# STM32-ROMI_Rev_A_2_3V_5V.net
KiCad netlist of a schematic drawn in Altium Designer
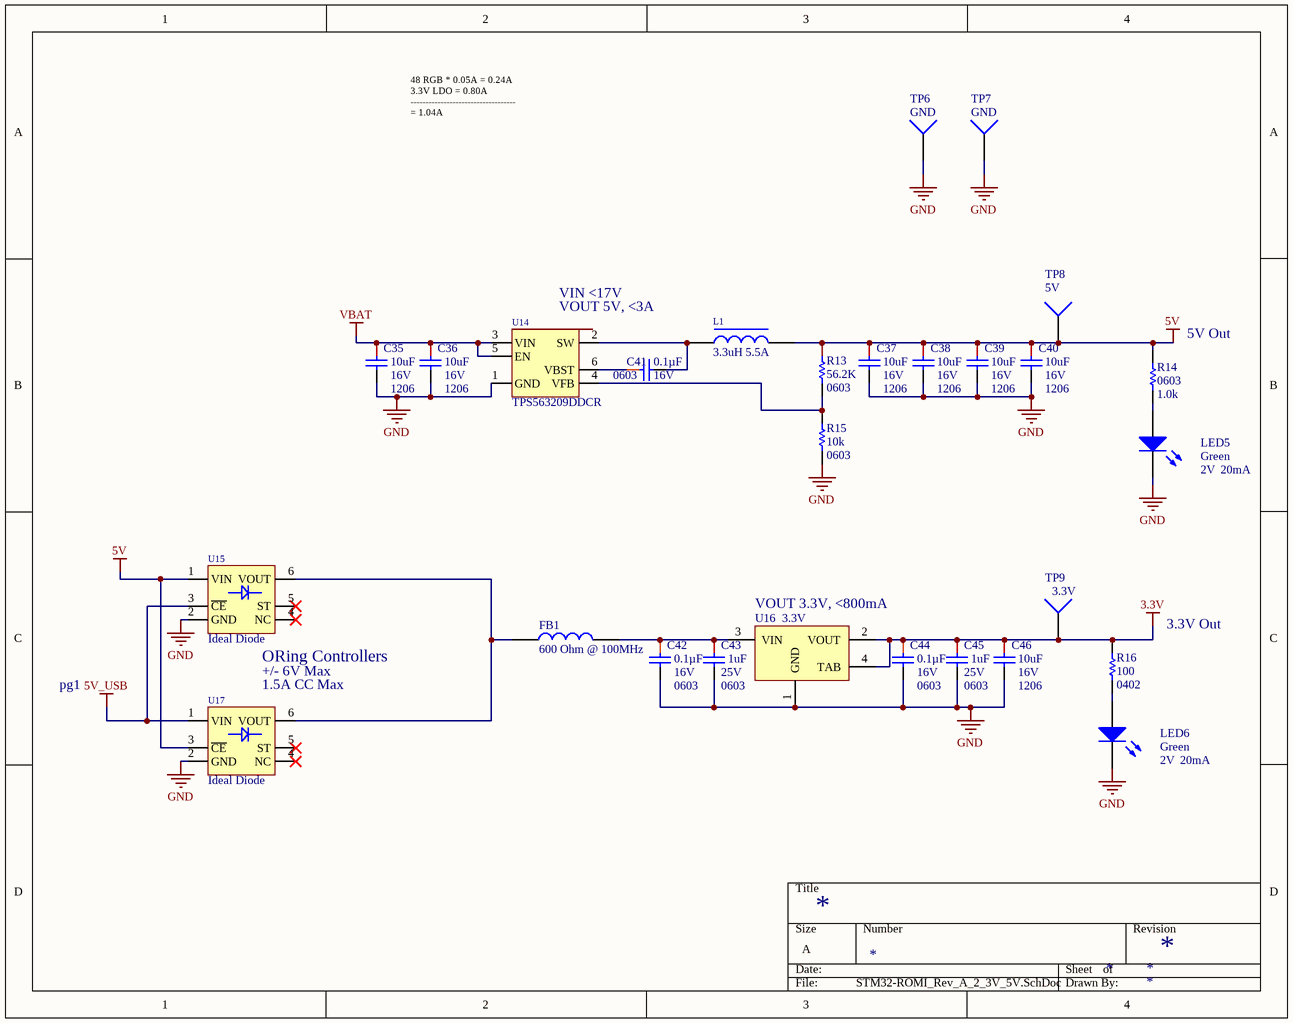
[diagram p0: STM32-ROMI_Rev_A_2_3V_5V.SchDoc]

(export (version "E")
  (design (tool "Eeschema 10.0.6"))
  (components
    (comp (ref "C35")
      (value "10uF")
      (footprint "CAPC1206(3216)_M")
      (fields (field (name "VOLTAGE - RATED") "16V") (field (name "PACKAGE") "1206"))
      (libsource (lib "Kyle-Passive") (part "CAP CER 10UF 16V 1206"))
    )
    (comp (ref "C36")
      (value "10uF")
      (footprint "CAPC1206(3216)_M")
      (fields (field (name "VOLTAGE - RATED") "16V") (field (name "PACKAGE") "1206"))
      (libsource (lib "Kyle-Passive") (part "CAP CER 10UF 16V 1206"))
    )
    (comp (ref "C37")
      (value "10uF")
      (footprint "CAPC1206(3216)_M")
      (fields (field (name "VOLTAGE - RATED") "16V") (field (name "PACKAGE") "1206"))
      (libsource (lib "Kyle-Passive") (part "CAP CER 10UF 16V 1206"))
    )
    (comp (ref "C38")
      (value "10uF")
      (footprint "CAPC1206(3216)_M")
      (fields (field (name "VOLTAGE - RATED") "16V") (field (name "PACKAGE") "1206"))
      (libsource (lib "Kyle-Passive") (part "CAP CER 10UF 16V 1206"))
    )
    (comp (ref "C39")
      (value "10uF")
      (footprint "CAPC1206(3216)_M")
      (fields (field (name "VOLTAGE - RATED") "16V") (field (name "PACKAGE") "1206"))
      (libsource (lib "Kyle-Passive") (part "CAP CER 10UF 16V 1206"))
    )
    (comp (ref "C40")
      (value "10uF")
      (footprint "CAPC1206(3216)_M")
      (fields (field (name "VOLTAGE - RATED") "16V") (field (name "PACKAGE") "1206"))
      (libsource (lib "Kyle-Passive") (part "CAP CER 10UF 16V 1206"))
    )
    (comp (ref "C41")
      (value "0.1uF")
      (footprint "CAPC0603(1608)_L")
      (description "0.1uF 0603 16V")
      (fields
        (field (name "MANUFACTURER") "Kemet")
        (field (name "MANUFACTURER PART NUMBER") "C0603C104K4RACTU")
        (field (name "CAPACITANCE") "0.1µF")
        (field (name "PACKAGE / CASE") "0603")
        (field (name "VOLTAGE - RATED") "16V")
      )
      (libsource (lib "Kyle-Passive") (part "CAP CER 0.1UF 16V 10% X7R 0603"))
    )
    (comp (ref "C42")
      (value "0.1uF")
      (footprint "CAPC0603(1608)_L")
      (description "0.1uF 0603 16V")
      (fields
        (field (name "MANUFACTURER") "Kemet")
        (field (name "MANUFACTURER PART NUMBER") "C0603C104K4RACTU")
        (field (name "CAPACITANCE") "0.1µF")
        (field (name "PACKAGE / CASE") "0603")
        (field (name "VOLTAGE - RATED") "16V")
      )
      (libsource (lib "Kyle-Passive") (part "CAP CER 0.1UF 16V 10% X7R 0603"))
    )
    (comp (ref "C43")
      (value "1uF")
      (footprint "CAPC0603(1608)_N")
      (description "1uF 0603 25V")
      (fields
        (field (name "MANUFACTURER") "TDK Corporation")
        (field (name "MANUFACTURER PART NUMBER") "CGA3E1X7R1E105K080AC")
        (field (name "VOLTAGE - RATED") "25V")
        (field (name "PACKAGE / CASE") "0603")
      )
      (libsource (lib "OLogic-Passive") (part "CAP CER 1UF 25V 10% X7R 0603"))
    )
    (comp (ref "C44")
      (value "0.1uF")
      (footprint "CAPC0603(1608)_L")
      (description "0.1uF 0603 16V")
      (fields
        (field (name "MANUFACTURER") "Kemet")
        (field (name "MANUFACTURER PART NUMBER") "C0603C104K4RACTU")
        (field (name "CAPACITANCE") "0.1µF")
        (field (name "PACKAGE / CASE") "0603")
        (field (name "VOLTAGE - RATED") "16V")
      )
      (libsource (lib "Kyle-Passive") (part "CAP CER 0.1UF 16V 10% X7R 0603"))
    )
    (comp (ref "C45")
      (value "1uF")
      (footprint "CAPC0603(1608)_N")
      (description "1uF 0603 25V")
      (fields
        (field (name "MANUFACTURER") "TDK Corporation")
        (field (name "MANUFACTURER PART NUMBER") "CGA3E1X7R1E105K080AC")
        (field (name "VOLTAGE - RATED") "25V")
        (field (name "PACKAGE / CASE") "0603")
      )
      (libsource (lib "OLogic-Passive") (part "CAP CER 1UF 25V 10% X7R 0603"))
    )
    (comp (ref "C46")
      (value "10uF")
      (footprint "CAPC1206(3216)_M")
      (fields (field (name "VOLTAGE - RATED") "16V") (field (name "PACKAGE") "1206"))
      (libsource (lib "Kyle-Passive") (part "CAP CER 10UF 16V 1206"))
    )
    (comp (ref "FB1")
      (value "600 Ohm @ 100MHz")
      (footprint "RESC0805(2012)_N")
      (description "600 OHM 0805 2.0A")
      (fields
        (field (name "MANUFACTURER") "Wurth Electronics Inc")
        (field (name "MANUFACTURER PART NUMBER") "742792040")
        (field (name "CREATOR") "osman")
      )
      (libsource (lib "OLogic-Passive") (part "FERRITE 600 OHM 2.0A 0805"))
    )
    (comp (ref "L1")
      (value "3.3uH 5.5A")
      (footprint "YSPI0530-3R3M")
      (description "Power Inductors 3.3uH ±20% 5.5A SMD,5.2x4.7x3mm RoHS")
      (fields (field (name "MANUFACTURER PART") "YSPI0530-3R3M"))
      (libsource (lib "Kyle-Passive") (part "FIXED IND 3.3UH 5.5A 28 MOHM SMD"))
    )
    (comp (ref "LED5")
      (value "G")
      (footprint "SM-LED-0603")
      (description "LED GREEN CLEAR THIN 0603 SMD")
      (fields
        (field (name "MANUFACTURER") "Lite-On Inc")
        (field (name "MANUFACTURER PART NUMBER") "LTST-C191KGKT")
        (field (name "COLOR") "Green")
        (field (name "VOLTAGE - FORWARD (VF) (TYP)") "2V")
        (field (name "CURRENT - TEST") "20mA")
      )
      (libsource (lib "Kyle-Diode-Opto-LED") (part "LTST-C191KGKT"))
    )
    (comp (ref "LED6")
      (value "G")
      (footprint "SM-LED-0603")
      (description "LED GREEN CLEAR THIN 0603 SMD")
      (fields
        (field (name "MANUFACTURER") "Lite-On Inc")
        (field (name "MANUFACTURER PART NUMBER") "LTST-C191KGKT")
        (field (name "COLOR") "Green")
        (field (name "VOLTAGE - FORWARD (VF) (TYP)") "2V")
        (field (name "CURRENT - TEST") "20mA")
      )
      (libsource (lib "Kyle-Diode-Opto-LED") (part "LTST-C191KGKT"))
    )
    (comp (ref "R13")
      (value "56.2K")
      (footprint "RESC0603(1608)_L")
      (description "RES SMD 56.2K OHM 1% 1/10W 0603")
      (fields (field (name "PACKAGE / CASE") "0603"))
      (libsource (lib "Kyle-Passive") (part "RES SMD 56.2K OHM 1% 1/10W 0603"))
    )
    (comp (ref "R14")
      (value "1.0K")
      (footprint "RESC0603(1608)_N")
      (description "1.0K 0603")
      (fields
        (field (name "MANUFACTURER") "Stackpole Electronics Inc.")
        (field (name "MANUFACTURER PART NUMBER") "RMCF0603FT1K00")
        (field (name "PACKAGE / CASE") "0603")
        (field (name "RESISTANCE (OHMS)") "1.0k")
      )
      (libsource (lib "Kyle-Passive") (part "RES 1K OHM 1% 1/10W 0603"))
    )
    (comp (ref "R15")
      (value "10K 1%")
      (footprint "RESC0603(1608)_L")
      (description "10K 0603")
      (fields
        (field (name "MANUFACTURER") "Panasonic Electronic Components")
        (field (name "MANUFACTURER PART NUMBER") "ERJ-3EKF1002V")
        (field (name "RESISTANCE (OHMS)") "10k")
        (field (name "PACKAGE / CASE") "0603")
      )
      (libsource (lib "Kyle-Passive") (part "RES 10K OHM 1/10W 1% 0603 SMD"))
    )
    (comp (ref "R16")
      (value "100")
      (footprint "RESC0402(1005)_N")
      (description "100 0402")
      (fields
        (field (name "MANUFACTURER") "Yageo")
        (field (name "MANUFACTURER PART NUMBER") "RC0402FR-07100RL")
        (field (name "SUPPLIER DEVICE PACKAGE") "0402")
      )
      (libsource (lib "OLogic-Passive") (part "RES 100 OHM 1% 1/16W 0402"))
    )
    (comp (ref "TP6")
      (value "GND")
      (footprint "TestPoint-MD")
      (description "Test Point")
      (libsource (lib "Kyle-Misc") (part "TestPoint"))
    )
    (comp (ref "TP7")
      (value "GND")
      (footprint "TestPoint-MD")
      (description "Test Point")
      (libsource (lib "Kyle-Misc") (part "TestPoint"))
    )
    (comp (ref "TP8")
      (value "5V")
      (footprint "TestPoint-MD")
      (description "Test Point")
      (libsource (lib "Kyle-Misc") (part "TestPoint"))
    )
    (comp (ref "TP9")
      (value "3.3V")
      (footprint "TestPoint-MD")
      (description "Test Point")
      (libsource (lib "Kyle-Misc") (part "TestPoint"))
    )
    (comp (ref "U14")
      (value "TPS563209DDCR")
      (footprint "SOT-23")
      (description "IC REG BUCK ADJ 3A TSOT23-6")
      (libsource (lib "Kyle-Reg-Convert") (part "TPS563209DDCR"))
    )
    (comp (ref "U15")
      (value "Ideal Diode")
      (footprint "SC-70-6")
      (description "OR Controller P-Channel 1.5A CC")
      (libsource (lib "Kyle-Reg-Convert") (part "LM66100DCKT"))
    )
    (comp (ref "U16")
      (value "3.3V")
      (footprint "DSO-G3")
      (description "3.3 volt fixed regulator, 800mA")
      (libsource (lib "OLogic-Reg-Convert") (part "LD1117S33"))
    )
    (comp (ref "U17")
      (value "Ideal Diode")
      (footprint "SC-70-6")
      (description "OR Controller P-Channel 1.5A CC")
      (libsource (lib "Kyle-Reg-Convert") (part "LM66100DCKT"))
    )
  )
  (nets
    (net (code "1") (name "3.3V") (class "Default")
      (node (ref "C44") (pin "1") (pinfunction "1_1") (pintype "passive"))
      (node (ref "C45") (pin "1") (pinfunction "1_1") (pintype "passive"))
      (node (ref "C46") (pin "1") (pinfunction "1_1") (pintype "passive"))
      (node (ref "R16") (pin "2") (pinfunction "2_2") (pintype "passive"))
      (node (ref "TP9") (pin "1") (pinfunction "1_1") (pintype "passive"))
      (node (ref "U16") (pin "2") (pinfunction "VOUT_2") (pintype "power_in"))
      (node (ref "U16") (pin "4") (pinfunction "TAB_4") (pintype "power_in"))
    )
    (net (code "2") (name "5V") (class "Default")
      (node (ref "C37") (pin "1") (pinfunction "1_1") (pintype "passive"))
      (node (ref "C38") (pin "1") (pinfunction "1_1") (pintype "passive"))
      (node (ref "C39") (pin "1") (pinfunction "1_1") (pintype "passive"))
      (node (ref "C40") (pin "1") (pinfunction "1_1") (pintype "passive"))
      (node (ref "L1") (pin "2") (pinfunction "2_2") (pintype "passive"))
      (node (ref "R13") (pin "1") (pinfunction "1_1") (pintype "passive"))
      (node (ref "R14") (pin "2") (pinfunction "2_2") (pintype "passive"))
      (node (ref "TP8") (pin "1") (pinfunction "1_1") (pintype "passive"))
      (node (ref "U15") (pin "1") (pinfunction "VIN_1") (pintype "passive"))
      (node (ref "U17") (pin "3") (pinfunction "~{CE}_3") (pintype "passive"))
    )
    (net (code "3") (name "5V_USB") (class "Default")
      (node (ref "U15") (pin "3") (pinfunction "~{CE}_3") (pintype "passive"))
      (node (ref "U17") (pin "1") (pinfunction "VIN_1") (pintype "passive"))
    )
    (net (code "4") (name "GND") (class "Default")
      (node (ref "C35") (pin "2") (pinfunction "2_2") (pintype "passive"))
      (node (ref "C36") (pin "2") (pinfunction "2_2") (pintype "passive"))
      (node (ref "C37") (pin "2") (pinfunction "2_2") (pintype "passive"))
      (node (ref "C38") (pin "2") (pinfunction "2_2") (pintype "passive"))
      (node (ref "C39") (pin "2") (pinfunction "2_2") (pintype "passive"))
      (node (ref "C40") (pin "2") (pinfunction "2_2") (pintype "passive"))
      (node (ref "C42") (pin "2") (pinfunction "2_2") (pintype "passive"))
      (node (ref "C43") (pin "2") (pinfunction "2_2") (pintype "passive"))
      (node (ref "C44") (pin "2") (pinfunction "2_2") (pintype "passive"))
      (node (ref "C45") (pin "2") (pinfunction "2_2") (pintype "passive"))
      (node (ref "C46") (pin "2") (pinfunction "2_2") (pintype "passive"))
      (node (ref "LED5") (pin "2") (pinfunction "2_2") (pintype "passive"))
      (node (ref "LED6") (pin "2") (pinfunction "2_2") (pintype "passive"))
      (node (ref "R15") (pin "1") (pinfunction "1_1") (pintype "passive"))
      (node (ref "TP6") (pin "1") (pinfunction "1_1") (pintype "passive"))
      (node (ref "TP7") (pin "1") (pinfunction "1_1") (pintype "passive"))
      (node (ref "U14") (pin "1") (pinfunction "GND_1") (pintype "power_in"))
      (node (ref "U15") (pin "2") (pinfunction "GND_2") (pintype "passive"))
      (node (ref "U16") (pin "1") (pinfunction "GND_1") (pintype "power_in"))
      (node (ref "U17") (pin "2") (pinfunction "GND_2") (pintype "passive"))
    )
    (net (code "5") (name "Net-(LED5-Pad1)") (class "Default")
      (node (ref "LED5") (pin "1") (pinfunction "1_1") (pintype "passive"))
      (node (ref "R14") (pin "1") (pinfunction "1_1") (pintype "passive"))
    )
    (net (code "6") (name "Net-(LED6-Pad1)") (class "Default")
      (node (ref "LED6") (pin "1") (pinfunction "1_1") (pintype "passive"))
      (node (ref "R16") (pin "1") (pinfunction "1_1") (pintype "passive"))
    )
    (net (code "7") (name "Net-(U14-SW)") (class "Default")
      (node (ref "C41") (pin "2") (pinfunction "2_2") (pintype "passive"))
      (node (ref "L1") (pin "1") (pinfunction "1_1") (pintype "passive"))
      (node (ref "U14") (pin "2") (pinfunction "SW_2") (pintype "power_in"))
    )
    (net (code "8") (name "Net-(U14-VBST)") (class "Default")
      (node (ref "C41") (pin "1") (pinfunction "1_1") (pintype "passive"))
      (node (ref "U14") (pin "6") (pinfunction "VBST_6") (pintype "power_in"))
    )
    (net (code "9") (name "Net-(U14-VFB)") (class "Default")
      (node (ref "R13") (pin "2") (pinfunction "2_2") (pintype "passive"))
      (node (ref "R15") (pin "2") (pinfunction "2_2") (pintype "passive"))
      (node (ref "U14") (pin "4") (pinfunction "VFB_4") (pintype "power_in"))
    )
    (net (code "10") (name "Net-(U15-VOUT)") (class "Default")
      (node (ref "FB1") (pin "1") (pinfunction "1_1") (pintype "passive"))
      (node (ref "U15") (pin "6") (pinfunction "VOUT_6") (pintype "passive"))
      (node (ref "U17") (pin "6") (pinfunction "VOUT_6") (pintype "passive"))
    )
    (net (code "11") (name "Net-(U16-VIN)") (class "Default")
      (node (ref "C42") (pin "1") (pinfunction "1_1") (pintype "passive"))
      (node (ref "C43") (pin "1") (pinfunction "1_1") (pintype "passive"))
      (node (ref "FB1") (pin "2") (pinfunction "2_2") (pintype "passive"))
      (node (ref "U16") (pin "3") (pinfunction "VIN_3") (pintype "power_in"))
    )
    (net (code "12") (name "VBAT") (class "Default")
      (node (ref "C35") (pin "1") (pinfunction "1_1") (pintype "passive"))
      (node (ref "C36") (pin "1") (pinfunction "1_1") (pintype "passive"))
      (node (ref "U14") (pin "3") (pinfunction "VIN_3") (pintype "power_in"))
      (node (ref "U14") (pin "5") (pinfunction "EN_5") (pintype "power_in"))
    )
    (net (code "13") (name "unconnected-(U15-NC-Pad4)") (class "Default")
      (node (ref "U15") (pin "4") (pinfunction "NC_4") (pintype "passive+no_connect"))
    )
    (net (code "14") (name "unconnected-(U15-ST-Pad5)") (class "Default")
      (node (ref "U15") (pin "5") (pinfunction "ST_5") (pintype "passive+no_connect"))
    )
    (net (code "15") (name "unconnected-(U17-NC-Pad4)") (class "Default")
      (node (ref "U17") (pin "4") (pinfunction "NC_4") (pintype "passive+no_connect"))
    )
    (net (code "16") (name "unconnected-(U17-ST-Pad5)") (class "Default")
      (node (ref "U17") (pin "5") (pinfunction "ST_5") (pintype "passive+no_connect"))
    )
  )
)
